# power-motor.net
KiCad netlist of a schematic drawn in EAGLE
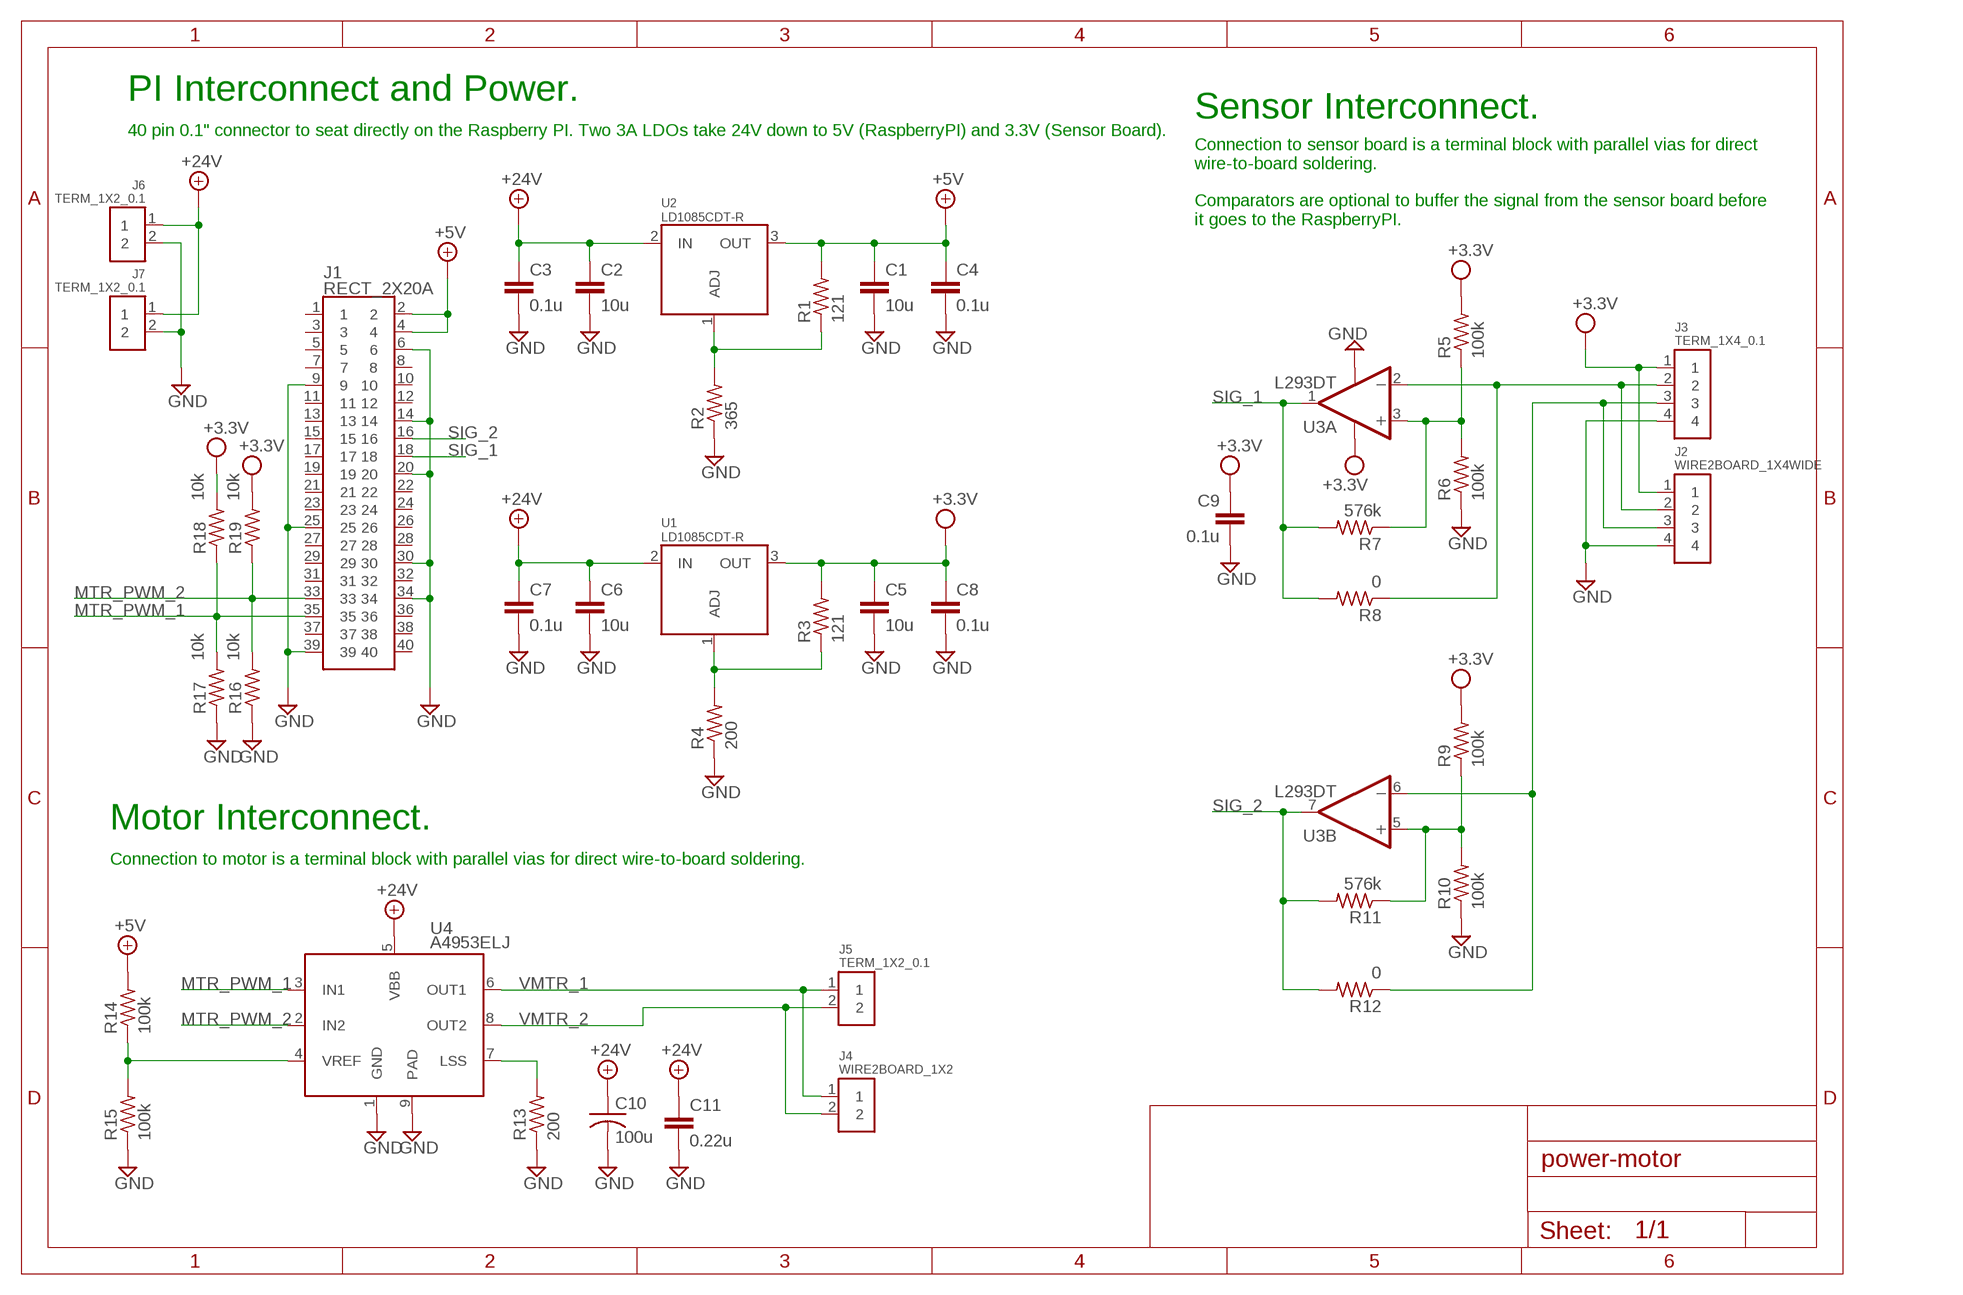
[diagram p0: schematic, sheet 1]

(export (version "E")
  (design (tool "Eeschema 10.0.6"))
  (components
    (comp (ref "C1")
      (value "10u")
      (footprint "eagle-import:C0805")
      (libsource (lib "eagle-import") (part "C0805"))
    )
    (comp (ref "C2")
      (value "10u")
      (footprint "eagle-import:C0805")
      (libsource (lib "eagle-import") (part "C0805"))
    )
    (comp (ref "C3")
      (value "0.1u")
      (footprint "eagle-import:C0805")
      (libsource (lib "eagle-import") (part "C0805"))
    )
    (comp (ref "C4")
      (value "0.1u")
      (footprint "eagle-import:C0805")
      (libsource (lib "eagle-import") (part "C0805"))
    )
    (comp (ref "C5")
      (value "10u")
      (footprint "eagle-import:C0805")
      (libsource (lib "eagle-import") (part "C0805"))
    )
    (comp (ref "C6")
      (value "10u")
      (footprint "eagle-import:C0805")
      (libsource (lib "eagle-import") (part "C0805"))
    )
    (comp (ref "C7")
      (value "0.1u")
      (footprint "eagle-import:C0805")
      (libsource (lib "eagle-import") (part "C0805"))
    )
    (comp (ref "C8")
      (value "0.1u")
      (footprint "eagle-import:C0805")
      (libsource (lib "eagle-import") (part "C0805"))
    )
    (comp (ref "C9")
      (value "0.1u")
      (footprint "eagle-import:C0805")
      (libsource (lib "eagle-import") (part "C0805"))
    )
    (comp (ref "C10")
      (value "100u")
      (footprint "eagle-import:CPOL-8")
      (libsource (lib "eagle-import") (part "C-POL8"))
    )
    (comp (ref "C11")
      (value "0.22u")
      (footprint "eagle-import:C0805")
      (libsource (lib "eagle-import") (part "C0805"))
    )
    (comp (ref "J1")
      (value "RECT_2X20A")
      (footprint "eagle-import:RECT_2X20_0.1")
      (libsource (lib "eagle-import") (part "RECT_2X20A"))
    )
    (comp (ref "J2")
      (value "WIRE2BOARD_1X4WIDE")
      (footprint "eagle-import:WIRE2BOARD_1X4W")
      (libsource (lib "eagle-import") (part "WIRE2BOARD_1X4WIDE"))
    )
    (comp (ref "J3")
      (value "TERM_1X4_0.1")
      (footprint "eagle-import:TERM_1X4_0.1")
      (libsource (lib "eagle-import") (part "TERM_1X4_0.1"))
    )
    (comp (ref "J4")
      (value "WIRE2BOARD_1X2")
      (footprint "eagle-import:WIRE2BOARD_1X2")
      (libsource (lib "eagle-import") (part "WIRE2BOARD_1X2"))
    )
    (comp (ref "J5")
      (value "TERM_1X2_0.1")
      (footprint "eagle-import:TERM_1X2_0.1")
      (libsource (lib "eagle-import") (part "TERM_1X2_0.1"))
    )
    (comp (ref "J6")
      (value "TERM_1X2_0.1")
      (footprint "eagle-import:TERM_1X2_0.1")
      (libsource (lib "eagle-import") (part "TERM_1X2_0.1"))
    )
    (comp (ref "J7")
      (value "TERM_1X2_0.1")
      (footprint "eagle-import:TERM_1X2_0.1")
      (libsource (lib "eagle-import") (part "TERM_1X2_0.1"))
    )
    (comp (ref "R1")
      (value "121")
      (footprint "eagle-import:R0805")
      (libsource (lib "eagle-import") (part "R0805"))
    )
    (comp (ref "R2")
      (value "365")
      (footprint "eagle-import:R0805")
      (libsource (lib "eagle-import") (part "R0805"))
    )
    (comp (ref "R3")
      (value "121")
      (footprint "eagle-import:R0805")
      (libsource (lib "eagle-import") (part "R0805"))
    )
    (comp (ref "R4")
      (value "200")
      (footprint "eagle-import:R0805")
      (libsource (lib "eagle-import") (part "R0805"))
    )
    (comp (ref "R5")
      (value "100k")
      (footprint "eagle-import:R0805")
      (libsource (lib "eagle-import") (part "R0805"))
    )
    (comp (ref "R6")
      (value "100k")
      (footprint "eagle-import:R0805")
      (libsource (lib "eagle-import") (part "R0805"))
    )
    (comp (ref "R7")
      (value "576k")
      (footprint "eagle-import:R0805")
      (libsource (lib "eagle-import") (part "R0805"))
    )
    (comp (ref "R8")
      (value "0")
      (footprint "eagle-import:R0805")
      (libsource (lib "eagle-import") (part "R0805"))
    )
    (comp (ref "R9")
      (value "100k")
      (footprint "eagle-import:R0805")
      (libsource (lib "eagle-import") (part "R0805"))
    )
    (comp (ref "R10")
      (value "100k")
      (footprint "eagle-import:R0805")
      (libsource (lib "eagle-import") (part "R0805"))
    )
    (comp (ref "R11")
      (value "576k")
      (footprint "eagle-import:R0805")
      (libsource (lib "eagle-import") (part "R0805"))
    )
    (comp (ref "R12")
      (value "0")
      (footprint "eagle-import:R0805")
      (libsource (lib "eagle-import") (part "R0805"))
    )
    (comp (ref "R13")
      (value "200")
      (footprint "eagle-import:R2512")
      (libsource (lib "eagle-import") (part "R2512"))
    )
    (comp (ref "R14")
      (value "100k")
      (footprint "eagle-import:R0805")
      (libsource (lib "eagle-import") (part "R0805"))
    )
    (comp (ref "R15")
      (value "100k")
      (footprint "eagle-import:R0805")
      (libsource (lib "eagle-import") (part "R0805"))
    )
    (comp (ref "R16")
      (value "10k")
      (footprint "eagle-import:R0805")
      (libsource (lib "eagle-import") (part "R0805"))
    )
    (comp (ref "R17")
      (value "10k")
      (footprint "eagle-import:R0805")
      (libsource (lib "eagle-import") (part "R0805"))
    )
    (comp (ref "R18")
      (value "10k")
      (footprint "eagle-import:R0805")
      (libsource (lib "eagle-import") (part "R0805"))
    )
    (comp (ref "R19")
      (value "10k")
      (footprint "eagle-import:R0805")
      (libsource (lib "eagle-import") (part "R0805"))
    )
    (comp (ref "U1")
      (value "LD1085CDT-R")
      (footprint "eagle-import:TO252")
      (libsource (lib "eagle-import") (part "LD1085CDT-R"))
    )
    (comp (ref "U2")
      (value "LD1085CDT-R")
      (footprint "eagle-import:TO252")
      (libsource (lib "eagle-import") (part "LD1085CDT-R"))
    )
    (comp (ref "U3")
      (value "L293DT")
      (footprint "eagle-import:SOIC8")
      (fields (field (name "DKPN") "497-8079-1-ND"))
      (libsource (lib "eagle-import") (part "L293DT"))
    )
    (comp (ref "U4")
      (value "A4953ELJ")
      (footprint "eagle-import:SOIC8")
      (libsource (lib "eagle-import") (part "A4953ELJ"))
    )
  )
  (nets
    (net (code "1") (name "+3.3V") (class "Default")
      (node (ref "C5") (pin "1") (pinfunction "1_1") (pintype "passive"))
      (node (ref "C8") (pin "1") (pinfunction "1_1") (pintype "passive"))
      (node (ref "C9") (pin "1") (pinfunction "1_1") (pintype "passive"))
      (node (ref "J2") (pin "1") (pinfunction "1_1") (pintype "bidirectional"))
      (node (ref "J3") (pin "1") (pinfunction "1_1") (pintype "bidirectional"))
      (node (ref "R18") (pin "2") (pinfunction "2_2") (pintype "passive"))
      (node (ref "R19") (pin "2") (pinfunction "2_2") (pintype "passive"))
      (node (ref "R3") (pin "2") (pinfunction "2_2") (pintype "passive"))
      (node (ref "R5") (pin "2") (pinfunction "2_2") (pintype "passive"))
      (node (ref "R9") (pin "2") (pinfunction "2_2") (pintype "passive"))
      (node (ref "U1") (pin "3") (pinfunction "OUT_3") (pintype "bidirectional"))
      (node (ref "U3") (pin "8") (pinfunction "V+_8") (pintype "power_in"))
    )
    (net (code "2") (name "+5V") (class "Default")
      (node (ref "C1") (pin "1") (pinfunction "1_1") (pintype "passive"))
      (node (ref "C4") (pin "1") (pinfunction "1_1") (pintype "passive"))
      (node (ref "J1") (pin "2") (pinfunction "2_2") (pintype "bidirectional"))
      (node (ref "J1") (pin "4") (pinfunction "4_4") (pintype "bidirectional"))
      (node (ref "R1") (pin "2") (pinfunction "2_2") (pintype "passive"))
      (node (ref "R14") (pin "2") (pinfunction "2_2") (pintype "passive"))
      (node (ref "U2") (pin "3") (pinfunction "OUT_3") (pintype "bidirectional"))
    )
    (net (code "3") (name "+24V") (class "Default")
      (node (ref "C10") (pin "P$1") (pinfunction "1_P$1") (pintype "passive"))
      (node (ref "C11") (pin "1") (pinfunction "1_1") (pintype "passive"))
      (node (ref "C2") (pin "1") (pinfunction "1_1") (pintype "passive"))
      (node (ref "C3") (pin "1") (pinfunction "1_1") (pintype "passive"))
      (node (ref "C6") (pin "1") (pinfunction "1_1") (pintype "passive"))
      (node (ref "C7") (pin "1") (pinfunction "1_1") (pintype "passive"))
      (node (ref "J6") (pin "1") (pinfunction "1_1") (pintype "bidirectional"))
      (node (ref "J7") (pin "1") (pinfunction "1_1") (pintype "bidirectional"))
      (node (ref "U1") (pin "2") (pinfunction "IN_2") (pintype "bidirectional"))
      (node (ref "U2") (pin "2") (pinfunction "IN_2") (pintype "bidirectional"))
      (node (ref "U4") (pin "5") (pinfunction "VBB_5") (pintype "bidirectional"))
    )
    (net (code "4") (name "/MTR_PWM_1") (class "Default")
      (node (ref "J1") (pin "35") (pinfunction "35_35") (pintype "bidirectional"))
      (node (ref "R17") (pin "2") (pinfunction "2_2") (pintype "passive"))
      (node (ref "R18") (pin "1") (pinfunction "1_1") (pintype "passive"))
      (node (ref "U4") (pin "3") (pinfunction "IN1_3") (pintype "bidirectional"))
    )
    (net (code "5") (name "/MTR_PWM_2") (class "Default")
      (node (ref "J1") (pin "33") (pinfunction "33_33") (pintype "bidirectional"))
      (node (ref "R16") (pin "2") (pinfunction "2_2") (pintype "passive"))
      (node (ref "R19") (pin "1") (pinfunction "1_1") (pintype "passive"))
      (node (ref "U4") (pin "2") (pinfunction "IN2_2") (pintype "bidirectional"))
    )
    (net (code "6") (name "/SIG_1") (class "Default")
      (node (ref "J1") (pin "18") (pinfunction "18_18") (pintype "bidirectional"))
      (node (ref "R7") (pin "2") (pinfunction "2_2") (pintype "passive"))
      (node (ref "R8") (pin "2") (pinfunction "2_2") (pintype "passive"))
      (node (ref "U3") (pin "1") (pinfunction "OUT_1") (pintype "output"))
    )
    (net (code "7") (name "/SIG_2") (class "Default")
      (node (ref "J1") (pin "16") (pinfunction "16_16") (pintype "bidirectional"))
      (node (ref "R11") (pin "2") (pinfunction "2_2") (pintype "passive"))
      (node (ref "R12") (pin "2") (pinfunction "2_2") (pintype "passive"))
      (node (ref "U3") (pin "7") (pinfunction "OUT_7") (pintype "output"))
    )
    (net (code "8") (name "/VMTR_1") (class "Default")
      (node (ref "J4") (pin "1") (pinfunction "1_1") (pintype "bidirectional"))
      (node (ref "J5") (pin "1") (pinfunction "1_1") (pintype "bidirectional"))
      (node (ref "U4") (pin "6") (pinfunction "OUT1_6") (pintype "bidirectional"))
    )
    (net (code "9") (name "/VMTR_2") (class "Default")
      (node (ref "J4") (pin "2") (pinfunction "2_2") (pintype "bidirectional"))
      (node (ref "J5") (pin "2") (pinfunction "2_2") (pintype "bidirectional"))
      (node (ref "U4") (pin "8") (pinfunction "OUT2_8") (pintype "bidirectional"))
    )
    (net (code "10") (name "GND") (class "Default")
      (node (ref "C1") (pin "2") (pinfunction "2_2") (pintype "passive"))
      (node (ref "C10") (pin "P$2") (pinfunction "2_P$2") (pintype "passive"))
      (node (ref "C11") (pin "2") (pinfunction "2_2") (pintype "passive"))
      (node (ref "C2") (pin "2") (pinfunction "2_2") (pintype "passive"))
      (node (ref "C3") (pin "2") (pinfunction "2_2") (pintype "passive"))
      (node (ref "C4") (pin "2") (pinfunction "2_2") (pintype "passive"))
      (node (ref "C5") (pin "2") (pinfunction "2_2") (pintype "passive"))
      (node (ref "C6") (pin "2") (pinfunction "2_2") (pintype "passive"))
      (node (ref "C7") (pin "2") (pinfunction "2_2") (pintype "passive"))
      (node (ref "C8") (pin "2") (pinfunction "2_2") (pintype "passive"))
      (node (ref "C9") (pin "2") (pinfunction "2_2") (pintype "passive"))
      (node (ref "J1") (pin "14") (pinfunction "14_14") (pintype "bidirectional"))
      (node (ref "J1") (pin "20") (pinfunction "20_20") (pintype "bidirectional"))
      (node (ref "J1") (pin "25") (pinfunction "25_25") (pintype "bidirectional"))
      (node (ref "J1") (pin "30") (pinfunction "30_30") (pintype "bidirectional"))
      (node (ref "J1") (pin "34") (pinfunction "34_34") (pintype "bidirectional"))
      (node (ref "J1") (pin "39") (pinfunction "39_39") (pintype "bidirectional"))
      (node (ref "J1") (pin "6") (pinfunction "6_6") (pintype "bidirectional"))
      (node (ref "J1") (pin "9") (pinfunction "9_9") (pintype "bidirectional"))
      (node (ref "J2") (pin "4") (pinfunction "4_4") (pintype "bidirectional"))
      (node (ref "J3") (pin "4") (pinfunction "4_4") (pintype "bidirectional"))
      (node (ref "J6") (pin "2") (pinfunction "2_2") (pintype "bidirectional"))
      (node (ref "J7") (pin "2") (pinfunction "2_2") (pintype "bidirectional"))
      (node (ref "R10") (pin "1") (pinfunction "1_1") (pintype "passive"))
      (node (ref "R13") (pin "1") (pinfunction "1_1") (pintype "passive"))
      (node (ref "R15") (pin "1") (pinfunction "1_1") (pintype "passive"))
      (node (ref "R16") (pin "1") (pinfunction "1_1") (pintype "passive"))
      (node (ref "R17") (pin "1") (pinfunction "1_1") (pintype "passive"))
      (node (ref "R2") (pin "1") (pinfunction "1_1") (pintype "passive"))
      (node (ref "R4") (pin "1") (pinfunction "1_1") (pintype "passive"))
      (node (ref "R6") (pin "1") (pinfunction "1_1") (pintype "passive"))
      (node (ref "U3") (pin "4") (pinfunction "V-_4") (pintype "power_in"))
      (node (ref "U4") (pin "1") (pinfunction "GND_1") (pintype "bidirectional"))
      (node (ref "U4") (pin "9") (pinfunction "PAD_9") (pintype "bidirectional"))
    )
    (net (code "11") (name "Net-(U1-ADJ)") (class "Default")
      (node (ref "R3") (pin "1") (pinfunction "1_1") (pintype "passive"))
      (node (ref "R4") (pin "2") (pinfunction "2_2") (pintype "passive"))
      (node (ref "U1") (pin "1") (pinfunction "ADJ_1") (pintype "bidirectional"))
    )
    (net (code "12") (name "Net-(U2-ADJ)") (class "Default")
      (node (ref "R1") (pin "1") (pinfunction "1_1") (pintype "passive"))
      (node (ref "R2") (pin "2") (pinfunction "2_2") (pintype "passive"))
      (node (ref "U2") (pin "1") (pinfunction "ADJ_1") (pintype "bidirectional"))
    )
    (net (code "13") (name "Net-(U3A-+IN)") (class "Default")
      (node (ref "R5") (pin "1") (pinfunction "1_1") (pintype "passive"))
      (node (ref "R6") (pin "2") (pinfunction "2_2") (pintype "passive"))
      (node (ref "R7") (pin "1") (pinfunction "1_1") (pintype "passive"))
      (node (ref "U3") (pin "3") (pinfunction "+IN_3") (pintype "input"))
    )
    (net (code "14") (name "Net-(U3A--IN)") (class "Default")
      (node (ref "J2") (pin "2") (pinfunction "2_2") (pintype "bidirectional"))
      (node (ref "J3") (pin "2") (pinfunction "2_2") (pintype "bidirectional"))
      (node (ref "R8") (pin "1") (pinfunction "1_1") (pintype "passive"))
      (node (ref "U3") (pin "2") (pinfunction "-IN_2") (pintype "input"))
    )
    (net (code "15") (name "Net-(U3B-+IN)") (class "Default")
      (node (ref "R10") (pin "2") (pinfunction "2_2") (pintype "passive"))
      (node (ref "R11") (pin "1") (pinfunction "1_1") (pintype "passive"))
      (node (ref "R9") (pin "1") (pinfunction "1_1") (pintype "passive"))
      (node (ref "U3") (pin "5") (pinfunction "+IN_5") (pintype "input"))
    )
    (net (code "16") (name "Net-(U3B--IN)") (class "Default")
      (node (ref "J2") (pin "3") (pinfunction "3_3") (pintype "bidirectional"))
      (node (ref "J3") (pin "3") (pinfunction "3_3") (pintype "bidirectional"))
      (node (ref "R12") (pin "1") (pinfunction "1_1") (pintype "passive"))
      (node (ref "U3") (pin "6") (pinfunction "-IN_6") (pintype "input"))
    )
    (net (code "17") (name "Net-(U4-LSS)") (class "Default")
      (node (ref "R13") (pin "2") (pinfunction "2_2") (pintype "passive"))
      (node (ref "U4") (pin "7") (pinfunction "LSS_7") (pintype "bidirectional"))
    )
    (net (code "18") (name "Net-(U4-VREF)") (class "Default")
      (node (ref "R14") (pin "1") (pinfunction "1_1") (pintype "passive"))
      (node (ref "R15") (pin "2") (pinfunction "2_2") (pintype "passive"))
      (node (ref "U4") (pin "4") (pinfunction "VREF_4") (pintype "bidirectional"))
    )
    (net (code "19") (name "unconnected-(J1-Pad1)") (class "Default")
      (node (ref "J1") (pin "1") (pinfunction "1_1") (pintype "bidirectional"))
    )
    (net (code "20") (name "unconnected-(J1-Pad3)") (class "Default")
      (node (ref "J1") (pin "3") (pinfunction "3_3") (pintype "bidirectional"))
    )
    (net (code "21") (name "unconnected-(J1-Pad5)") (class "Default")
      (node (ref "J1") (pin "5") (pinfunction "5_5") (pintype "bidirectional"))
    )
    (net (code "22") (name "unconnected-(J1-Pad7)") (class "Default")
      (node (ref "J1") (pin "7") (pinfunction "7_7") (pintype "bidirectional"))
    )
    (net (code "23") (name "unconnected-(J1-Pad8)") (class "Default")
      (node (ref "J1") (pin "8") (pinfunction "8_8") (pintype "bidirectional"))
    )
    (net (code "24") (name "unconnected-(J1-Pad10)") (class "Default")
      (node (ref "J1") (pin "10") (pinfunction "10_10") (pintype "bidirectional"))
    )
    (net (code "25") (name "unconnected-(J1-Pad11)") (class "Default")
      (node (ref "J1") (pin "11") (pinfunction "11_11") (pintype "bidirectional"))
    )
    (net (code "26") (name "unconnected-(J1-Pad12)") (class "Default")
      (node (ref "J1") (pin "12") (pinfunction "12_12") (pintype "bidirectional"))
    )
    (net (code "27") (name "unconnected-(J1-Pad13)") (class "Default")
      (node (ref "J1") (pin "13") (pinfunction "13_13") (pintype "bidirectional"))
    )
    (net (code "28") (name "unconnected-(J1-Pad15)") (class "Default")
      (node (ref "J1") (pin "15") (pinfunction "15_15") (pintype "bidirectional"))
    )
    (net (code "29") (name "unconnected-(J1-Pad17)") (class "Default")
      (node (ref "J1") (pin "17") (pinfunction "17_17") (pintype "bidirectional"))
    )
    (net (code "30") (name "unconnected-(J1-Pad19)") (class "Default")
      (node (ref "J1") (pin "19") (pinfunction "19_19") (pintype "bidirectional"))
    )
    (net (code "31") (name "unconnected-(J1-Pad21)") (class "Default")
      (node (ref "J1") (pin "21") (pinfunction "21_21") (pintype "bidirectional"))
    )
    (net (code "32") (name "unconnected-(J1-Pad22)") (class "Default")
      (node (ref "J1") (pin "22") (pinfunction "22_22") (pintype "bidirectional"))
    )
    (net (code "33") (name "unconnected-(J1-Pad23)") (class "Default")
      (node (ref "J1") (pin "23") (pinfunction "23_23") (pintype "bidirectional"))
    )
    (net (code "34") (name "unconnected-(J1-Pad24)") (class "Default")
      (node (ref "J1") (pin "24") (pinfunction "24_24") (pintype "bidirectional"))
    )
    (net (code "35") (name "unconnected-(J1-Pad26)") (class "Default")
      (node (ref "J1") (pin "26") (pinfunction "26_26") (pintype "bidirectional"))
    )
    (net (code "36") (name "unconnected-(J1-Pad27)") (class "Default")
      (node (ref "J1") (pin "27") (pinfunction "27_27") (pintype "bidirectional"))
    )
    (net (code "37") (name "unconnected-(J1-Pad28)") (class "Default")
      (node (ref "J1") (pin "28") (pinfunction "28_28") (pintype "bidirectional"))
    )
    (net (code "38") (name "unconnected-(J1-Pad29)") (class "Default")
      (node (ref "J1") (pin "29") (pinfunction "29_29") (pintype "bidirectional"))
    )
    (net (code "39") (name "unconnected-(J1-Pad31)") (class "Default")
      (node (ref "J1") (pin "31") (pinfunction "31_31") (pintype "bidirectional"))
    )
    (net (code "40") (name "unconnected-(J1-Pad32)") (class "Default")
      (node (ref "J1") (pin "32") (pinfunction "32_32") (pintype "bidirectional"))
    )
    (net (code "41") (name "unconnected-(J1-Pad36)") (class "Default")
      (node (ref "J1") (pin "36") (pinfunction "36_36") (pintype "bidirectional"))
    )
    (net (code "42") (name "unconnected-(J1-Pad37)") (class "Default")
      (node (ref "J1") (pin "37") (pinfunction "37_37") (pintype "bidirectional"))
    )
    (net (code "43") (name "unconnected-(J1-Pad38)") (class "Default")
      (node (ref "J1") (pin "38") (pinfunction "38_38") (pintype "bidirectional"))
    )
    (net (code "44") (name "unconnected-(J1-Pad40)") (class "Default")
      (node (ref "J1") (pin "40") (pinfunction "40_40") (pintype "bidirectional"))
    )
  )
)
